# Power_ICs.net
KiCad netlist of a schematic drawn in Altium Designer
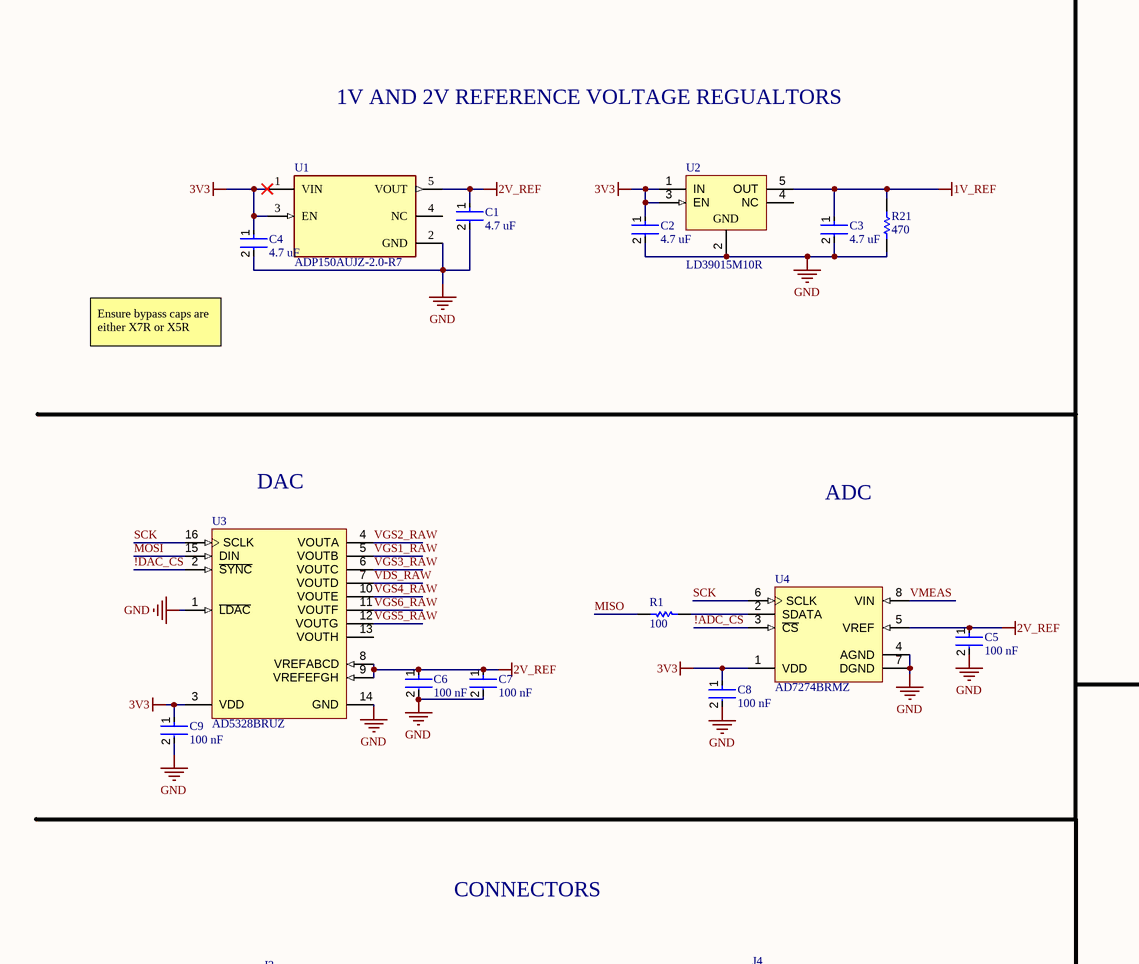
[diagram p0: Power+ICs.SchDoc, top left]
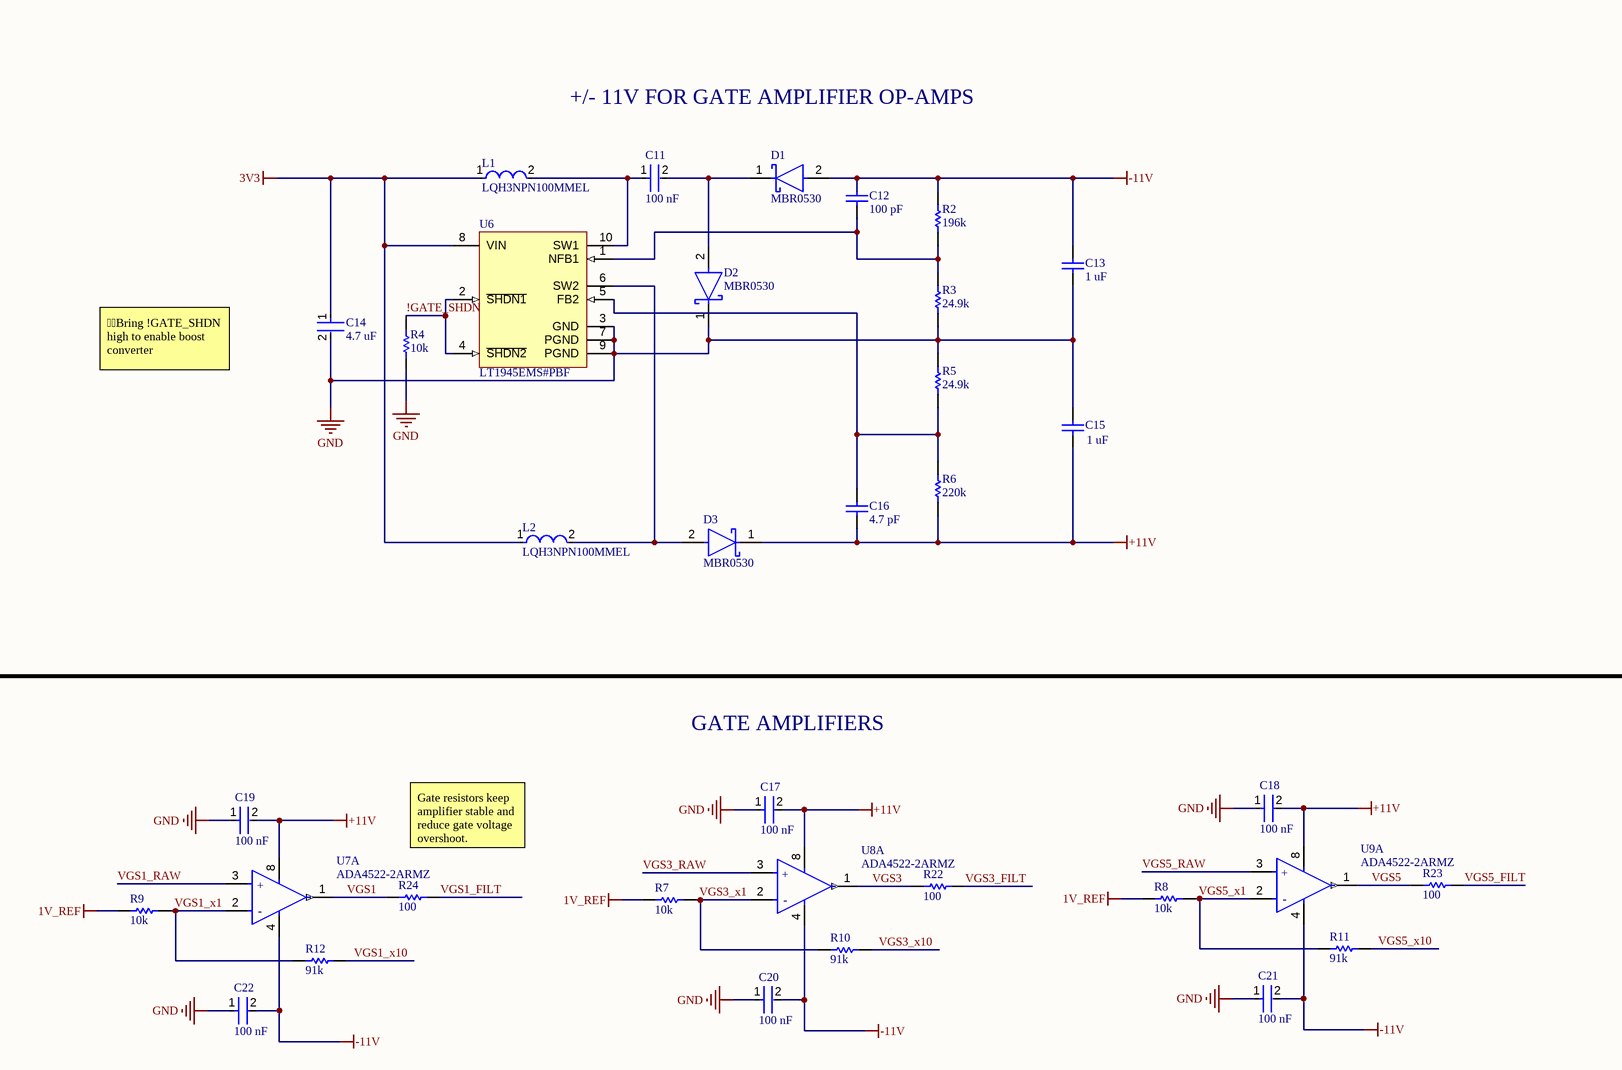
[diagram p1: Power+ICs.SchDoc, top right]
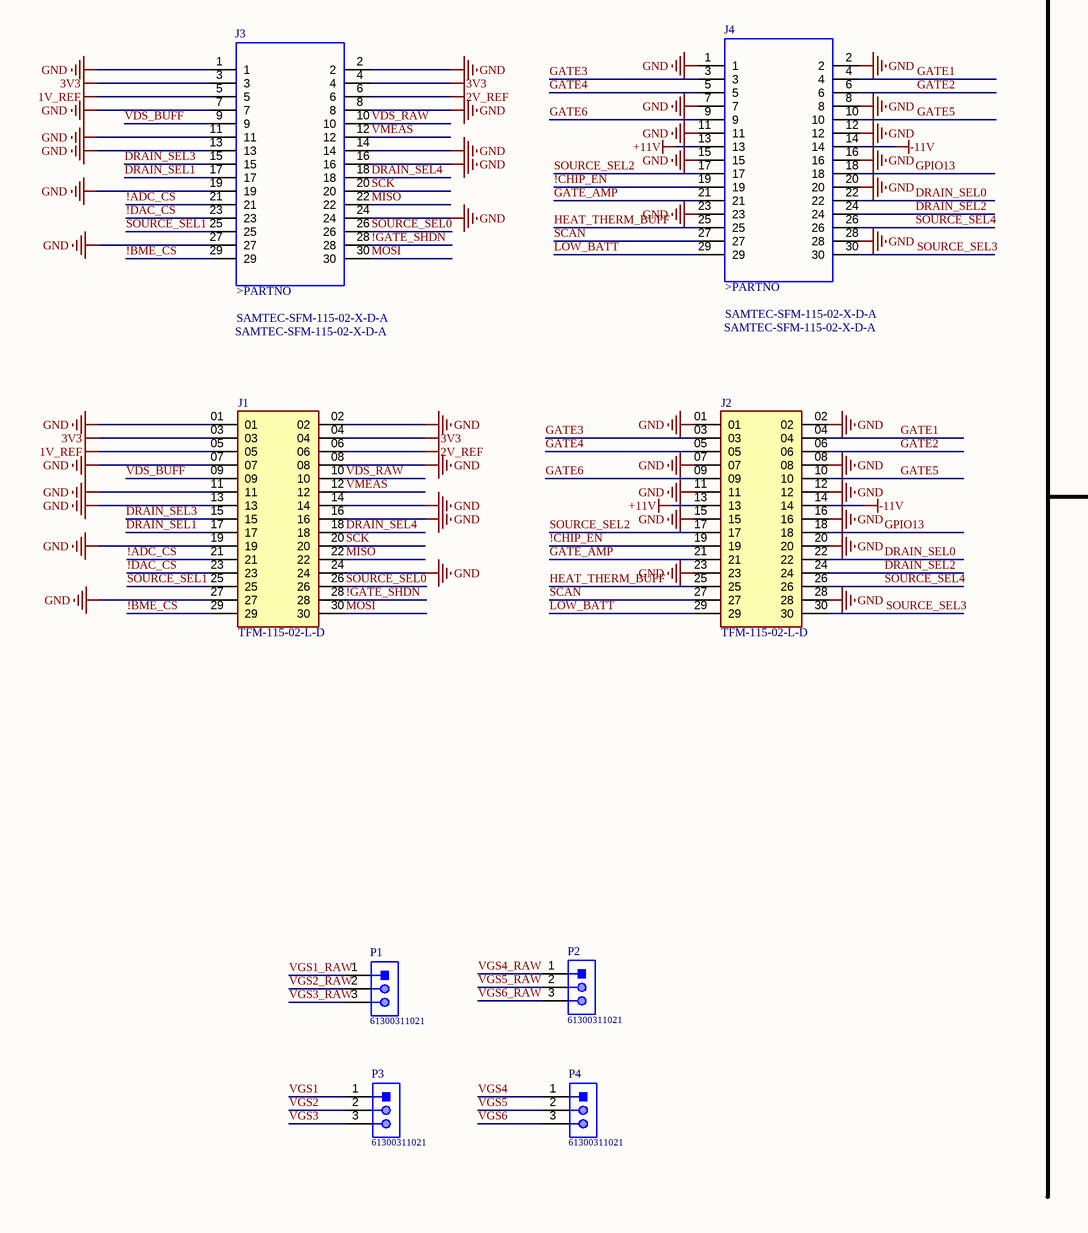
[diagram p2: Power+ICs.SchDoc, bottom left]
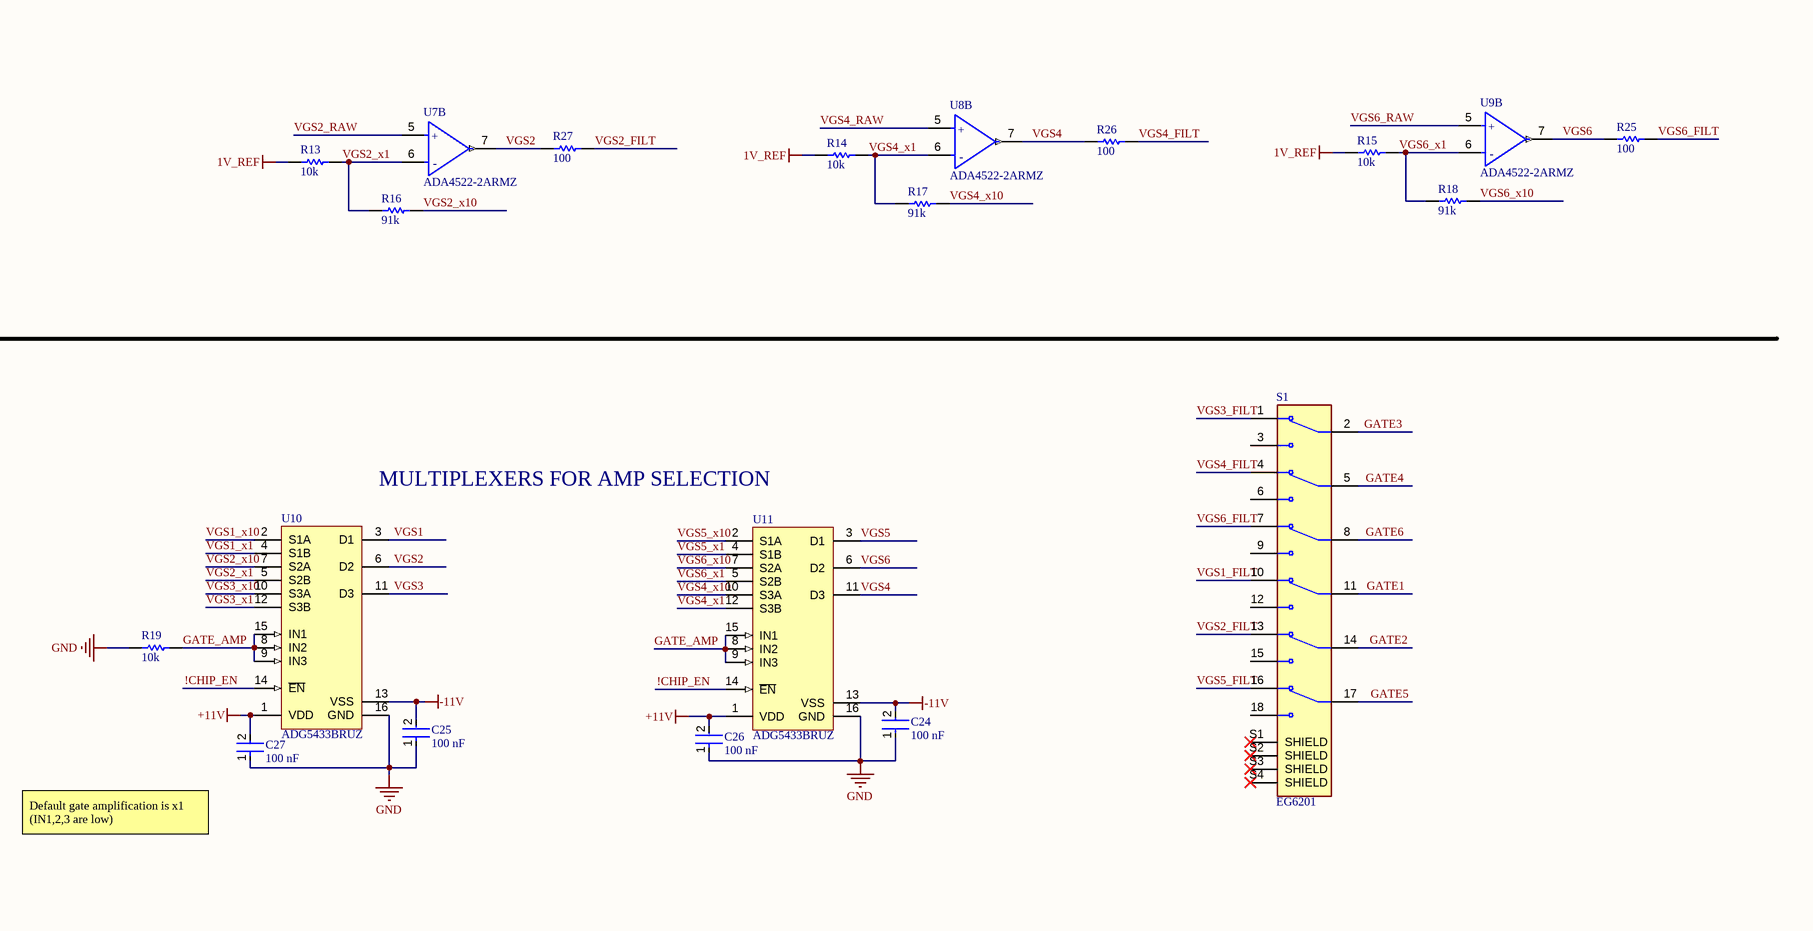
[diagram p3: Power+ICs.SchDoc, bottom right]

(export (version "E")
  (design (tool "Eeschema 10.0.6"))
  (components
    (comp (ref "C1")
      (value "4.7 uF")
      (footprint "FP-C0805C475K3PACTU-MFG")
      (description "CAP CER 4.7UF 25V X5R 0805")
      (fields (field (name "TOLERANCE") "10%") (field (name "VOLTAGE") "25V"))
      (libsource (lib "Altium Content Vault") (part "02cd4be3c70576c341d710602a673aa"))
    )
    (comp (ref "C2")
      (value "4.7 uF")
      (footprint "FP-C0805C475K3PACTU-MFG")
      (description "CAP CER 4.7UF 25V X5R 0805")
      (fields (field (name "TOLERANCE") "10%") (field (name "VOLTAGE") "25V"))
      (libsource (lib "Altium Content Vault") (part "02cd4be3c70576c341d710602a673aa"))
    )
    (comp (ref "C3")
      (value "4.7 uF")
      (footprint "FP-C0805C475K3PACTU-MFG")
      (description "CAP CER 4.7UF 25V X5R 0805")
      (fields (field (name "TOLERANCE") "10%") (field (name "VOLTAGE") "25V"))
      (libsource (lib "Altium Content Vault") (part "02cd4be3c70576c341d710602a673aa"))
    )
    (comp (ref "C4")
      (value "4.7 uF")
      (footprint "FP-C0805C475K3PACTU-MFG")
      (description "CAP CER 4.7UF 25V X5R 0805")
      (fields (field (name "TOLERANCE") "10%") (field (name "VOLTAGE") "25V"))
      (libsource (lib "Altium Content Vault") (part "02cd4be3c70576c341d710602a673aa"))
    )
    (comp (ref "C5")
      (value "100 nF")
      (footprint "FP-C0805C-DN-MFG")
      (description "CAP CER 0.1UF 50V X7R 0805")
      (fields
        (field (name "MANUFACTURER PART NUMBER") "C0805C104K5RACTU")
        (field (name "MANUFACTURER") "KEMET")
      )
      (libsource (lib "Altium Content Vault") (part "b4654b650e69147ec39a6b967a45e02"))
    )
    (comp (ref "C6")
      (value "100 nF")
      (footprint "FP-C0805C-DN-MFG")
      (description "CAP CER 0.1UF 50V X7R 0805")
      (fields
        (field (name "MANUFACTURER PART NUMBER") "C0805C104K5RACTU")
        (field (name "MANUFACTURER") "KEMET")
      )
      (libsource (lib "Altium Content Vault") (part "b4654b650e69147ec39a6b967a45e02"))
    )
    (comp (ref "C7")
      (value "100 nF")
      (footprint "FP-C0805C-DN-MFG")
      (description "CAP CER 0.1UF 50V X7R 0805")
      (fields
        (field (name "MANUFACTURER PART NUMBER") "C0805C104K5RACTU")
        (field (name "MANUFACTURER") "KEMET")
      )
      (libsource (lib "Altium Content Vault") (part "b4654b650e69147ec39a6b967a45e02"))
    )
    (comp (ref "C8")
      (value "100 nF")
      (footprint "FP-C0805C-DN-MFG")
      (description "CAP CER 0.1UF 50V X7R 0805")
      (fields
        (field (name "MANUFACTURER PART NUMBER") "C0805C104K5RACTU")
        (field (name "MANUFACTURER") "KEMET")
      )
      (libsource (lib "Altium Content Vault") (part "b4654b650e69147ec39a6b967a45e02"))
    )
    (comp (ref "C9")
      (value "100 nF")
      (footprint "FP-C0805C-DN-MFG")
      (description "CAP CER 0.1UF 50V X7R 0805")
      (fields
        (field (name "MANUFACTURER PART NUMBER") "C0805C104K5RACTU")
        (field (name "MANUFACTURER") "KEMET")
      )
      (libsource (lib "Altium Content Vault") (part "b4654b650e69147ec39a6b967a45e02"))
    )
    (comp (ref "C11")
      (value "100 nF")
      (footprint "FP-C0805C-DN-MFG")
      (description "CAP CER 0.1UF 50V X7R 0805")
      (fields
        (field (name "MANUFACTURER PART NUMBER") "C0805C104K5RACTU")
        (field (name "MANUFACTURER") "KEMET")
      )
      (libsource (lib "Altium Content Vault") (part "b4654b650e69147ec39a6b967a45e02"))
    )
    (comp (ref "C12")
      (value "100 pF")
      (footprint "CAPC2013X140X50ML20T25")
      (description "08055C101KAT2A")
      (fields (field (name "MANUFACTURER") "AVX Interconnect / Elco"))
      (libsource (lib "Altium Content Vault") (part "CAP"))
    )
    (comp (ref "C13")
      (value "1 uF")
      (footprint "CAPC3216X110X50LL20T25")
      (description "C1206C105K5RACTU")
      (fields (field (name "MANUFACTURER") "Kemet") (field (name "TOLERANCE") "10%"))
      (libsource (lib "Altium Content Vault") (part "CAP-NP-2"))
    )
    (comp (ref "C14")
      (value "4.7 uF")
      (footprint "FP-C0805C475K3PACTU-MFG")
      (description "CAP CER 4.7UF 25V X5R 0805")
      (fields (field (name "TOLERANCE") "10%") (field (name "VOLTAGE") "25V"))
      (libsource (lib "Altium Content Vault") (part "02cd4be3c70576c341d710602a673aa"))
    )
    (comp (ref "C15")
      (value "1 uF")
      (footprint "CAPC3216X110X50LL20T25")
      (description "C1206C105K5RACTU")
      (fields (field (name "MANUFACTURER") "Kemet") (field (name "TOLERANCE") "10%"))
      (libsource (lib "Altium Content Vault") (part "CAP-NP-2"))
    )
    (comp (ref "C16")
      (value "4.7 pF")
      (footprint "CAPC2013X71X50ML20T25")
      (description "08055A4R7CAT2A")
      (fields (field (name "MANUFACTURER") "AVX Interconnect / Elco"))
      (libsource (lib "Altium Content Vault") (part "CAP"))
    )
    (comp (ref "C17")
      (value "100 nF")
      (footprint "FP-C0805C-DN-MFG")
      (description "CAP CER 0.1UF 50V X7R 0805")
      (fields
        (field (name "MANUFACTURER PART NUMBER") "C0805C104K5RACTU")
        (field (name "MANUFACTURER") "KEMET")
      )
      (libsource (lib "Altium Content Vault") (part "b4654b650e69147ec39a6b967a45e02"))
    )
    (comp (ref "C18")
      (value "100 nF")
      (footprint "FP-C0805C-DN-MFG")
      (description "CAP CER 0.1UF 50V X7R 0805")
      (fields
        (field (name "MANUFACTURER PART NUMBER") "C0805C104K5RACTU")
        (field (name "MANUFACTURER") "KEMET")
      )
      (libsource (lib "Altium Content Vault") (part "b4654b650e69147ec39a6b967a45e02"))
    )
    (comp (ref "C19")
      (value "100 nF")
      (footprint "FP-C0805C-DN-MFG")
      (description "CAP CER 0.1UF 50V X7R 0805")
      (fields
        (field (name "MANUFACTURER PART NUMBER") "C0805C104K5RACTU")
        (field (name "MANUFACTURER") "KEMET")
      )
      (libsource (lib "Altium Content Vault") (part "b4654b650e69147ec39a6b967a45e02"))
    )
    (comp (ref "C20")
      (value "100 nF")
      (footprint "FP-C0805C-DN-MFG")
      (description "CAP CER 0.1UF 50V X7R 0805")
      (fields
        (field (name "MANUFACTURER PART NUMBER") "C0805C104K5RACTU")
        (field (name "MANUFACTURER") "KEMET")
      )
      (libsource (lib "Altium Content Vault") (part "b4654b650e69147ec39a6b967a45e02"))
    )
    (comp (ref "C21")
      (value "100 nF")
      (footprint "FP-C0805C-DN-MFG")
      (description "CAP CER 0.1UF 50V X7R 0805")
      (fields
        (field (name "MANUFACTURER PART NUMBER") "C0805C104K5RACTU")
        (field (name "MANUFACTURER") "KEMET")
      )
      (libsource (lib "Altium Content Vault") (part "b4654b650e69147ec39a6b967a45e02"))
    )
    (comp (ref "C22")
      (value "100 nF")
      (footprint "FP-C0805C-DN-MFG")
      (description "CAP CER 0.1UF 50V X7R 0805")
      (fields
        (field (name "MANUFACTURER PART NUMBER") "C0805C104K5RACTU")
        (field (name "MANUFACTURER") "KEMET")
      )
      (libsource (lib "Altium Content Vault") (part "b4654b650e69147ec39a6b967a45e02"))
    )
    (comp (ref "C24")
      (value "100 nF")
      (footprint "FP-C0805C-DN-MFG")
      (description "CAP CER 0.1UF 50V X7R 0805")
      (fields
        (field (name "MANUFACTURER PART NUMBER") "C0805C104K5RACTU")
        (field (name "MANUFACTURER") "KEMET")
      )
      (libsource (lib "Altium Content Vault") (part "b4654b650e69147ec39a6b967a45e02"))
    )
    (comp (ref "C25")
      (value "100 nF")
      (footprint "FP-C0805C-DN-MFG")
      (description "CAP CER 0.1UF 50V X7R 0805")
      (fields
        (field (name "MANUFACTURER PART NUMBER") "C0805C104K5RACTU")
        (field (name "MANUFACTURER") "KEMET")
      )
      (libsource (lib "Altium Content Vault") (part "b4654b650e69147ec39a6b967a45e02"))
    )
    (comp (ref "C26")
      (value "100 nF")
      (footprint "FP-C0805C-DN-MFG")
      (description "CAP CER 0.1UF 50V X7R 0805")
      (fields
        (field (name "MANUFACTURER PART NUMBER") "C0805C104K5RACTU")
        (field (name "MANUFACTURER") "KEMET")
      )
      (libsource (lib "Altium Content Vault") (part "b4654b650e69147ec39a6b967a45e02"))
    )
    (comp (ref "C27")
      (value "100 nF")
      (footprint "FP-C0805C-DN-MFG")
      (description "CAP CER 0.1UF 50V X7R 0805")
      (fields
        (field (name "MANUFACTURER PART NUMBER") "C0805C104K5RACTU")
        (field (name "MANUFACTURER") "KEMET")
      )
      (libsource (lib "Altium Content Vault") (part "b4654b650e69147ec39a6b967a45e02"))
    )
    (comp (ref "D1")
      (value "MBR0530")
      (footprint "FP-425-04-MFG")
      (description "DIODE SCHOTTKY 30V 500MA SOD123")
      (libsource (lib "Altium Content Vault") (part "1d6ec82d83fb6aee721767c19dac4b9"))
    )
    (comp (ref "D2")
      (value "MBR0530")
      (footprint "FP-425-04-MFG")
      (description "DIODE SCHOTTKY 30V 500MA SOD123")
      (libsource (lib "Altium Content Vault") (part "1d6ec82d83fb6aee721767c19dac4b9"))
    )
    (comp (ref "D3")
      (value "MBR0530")
      (footprint "FP-425-04-MFG")
      (description "DIODE SCHOTTKY 30V 500MA SOD123")
      (libsource (lib "Altium Content Vault") (part "1d6ec82d83fb6aee721767c19dac4b9"))
    )
    (comp (ref "J1")
      (value "TFM-115-02-L-D")
      (footprint "SAMTEC_TFM-115-02-L-D:SAMTEC_TFM-115-02-L-D")
      (fields (field (name "MF") "Samtec Inc."))
      (libsource (lib "TFM-115-02-L-D") (part "TFM-115-02-L-D"))
    )
    (comp (ref "J2")
      (value "TFM-115-02-L-D")
      (footprint "SAMTEC_TFM-115-02-L-D:SAMTEC_TFM-115-02-L-D")
      (fields (field (name "MF") "Samtec Inc."))
      (libsource (lib "TFM-115-02-L-D") (part "TFM-115-02-L-D"))
    )
    (comp (ref "J3")
      (value "SAMTEC-SFM-115-02-X-D-A")
      (footprint "SAMTEC-SFM-115-02-X-D-A:SAMTEC-SFM-115-02-X-D-A")
      (fields (field (name "MF") "Samtec Inc."))
      (libsource (lib "SAMTEC-SFM-115-02-X-D-A") (part "SAMTEC-SFM-115-02-X-D-A"))
    )
    (comp (ref "J4")
      (value "SAMTEC-SFM-115-02-X-D-A")
      (footprint "SAMTEC-SFM-115-02-X-D-A:SAMTEC-SFM-115-02-X-D-A")
      (fields (field (name "MF") "Samtec Inc."))
      (libsource (lib "SAMTEC-SFM-115-02-X-D-A") (part "SAMTEC-SFM-115-02-X-D-A"))
    )
    (comp (ref "L1")
      (value "LQH3NPN100MMEL")
      (footprint "FP-LQH3NPH_ME-MFG")
      (description "Wire Wound Ferrite Inductor for Power Lines 10μH ±20% 0.228Ω 1280mA 1212")
      (fields (field (name "TOLERANCE") "20%"))
      (libsource (lib "Altium Content Vault") (part "725321dda6339637d4d059423bc1c3c"))
    )
    (comp (ref "L2")
      (value "LQH3NPN100MMEL")
      (footprint "FP-LQH3NPH_ME-MFG")
      (description "Wire Wound Ferrite Inductor for Power Lines 10μH ±20% 0.228Ω 1280mA 1212")
      (fields (field (name "TOLERANCE") "20%"))
      (libsource (lib "Altium Content Vault") (part "725321dda6339637d4d059423bc1c3c"))
    )
    (comp (ref "P1")
      (value "61300311021")
      (footprint "61300311021")
      (description "THT Angled Pin Header WR-PHD, Pitch 2.54 mm, Single Row, 3 pins")
      (fields (field (name "MANUFACTURER") "Wurth Elektronik") (field (name "PUBLISHER") "WurthElektronik"))
      (libsource (lib "Altium Content Vault") (part "WE-CN-1P-M-R3"))
    )
    (comp (ref "P2")
      (value "61300311021")
      (footprint "61300311021")
      (description "THT Angled Pin Header WR-PHD, Pitch 2.54 mm, Single Row, 3 pins")
      (fields (field (name "MANUFACTURER") "Wurth Elektronik") (field (name "PUBLISHER") "WurthElektronik"))
      (libsource (lib "Altium Content Vault") (part "WE-CN-1P-M-R3"))
    )
    (comp (ref "P3")
      (value "61300311021")
      (footprint "61300311021")
      (description "THT Angled Pin Header WR-PHD, Pitch 2.54 mm, Single Row, 3 pins")
      (fields (field (name "MANUFACTURER") "Wurth Elektronik") (field (name "PUBLISHER") "WurthElektronik"))
      (libsource (lib "Altium Content Vault") (part "WE-CN-1P-M-R3"))
    )
    (comp (ref "P4")
      (value "61300311021")
      (footprint "61300311021")
      (description "THT Angled Pin Header WR-PHD, Pitch 2.54 mm, Single Row, 3 pins")
      (fields (field (name "MANUFACTURER") "Wurth Elektronik") (field (name "PUBLISHER") "WurthElektronik"))
      (libsource (lib "Altium Content Vault") (part "WE-CN-1P-M-R3"))
    )
    (comp (ref "R1")
      (value "100")
      (footprint "RESC2013X50X30LL20T20")
      (fields (field (name "MANUFACTURER") "Vishay Dale") (field (name "PART NUMBER") "CRCW0805100RFKEA"))
      (libsource (lib "Altium Content Vault") (part "RES"))
    )
    (comp (ref "R2")
      (value "196k")
      (footprint "RESC2013X50X30LL20T20")
      (fields (field (name "MANUFACTURER") "Vishay Dale") (field (name "PART NUMBER") "CRCW0805196KFKEA"))
      (libsource (lib "Altium Content Vault") (part "RES"))
    )
    (comp (ref "R3")
      (value "24.9k")
      (footprint "RESC2013X70X40LL20T20")
      (fields (field (name "PART NUMBER") "ERJ-6ENF2492V") (field (name "MANUFACTURER") "Panasonic"))
      (libsource (lib "Altium Content Vault") (part "RES"))
    )
    (comp (ref "R4")
      (value "10k")
      (footprint "RESC2013X60X35NL10T20")
      (description "Chip Resistor, 10 KOhm, +/- 1%, 0.125 W, -55 to 155 degC, 0805 (2012 Metric), RoHS, Tape and Reel")
      (fields (field (name "MANUFACTURER") "Yageo"))
      (libsource (lib "Altium Content Vault") (part "RES-2"))
    )
    (comp (ref "R5")
      (value "24.9k")
      (footprint "RESC2013X70X40LL20T20")
      (fields (field (name "PART NUMBER") "ERJ-6ENF2492V") (field (name "MANUFACTURER") "Panasonic"))
      (libsource (lib "Altium Content Vault") (part "RES"))
    )
    (comp (ref "R6")
      (value "220k")
      (footprint "RESC2013X70X40ML20T20")
      (fields (field (name "PART NUMBER") "ERJ6ENF2203V") (field (name "MANUFACTURER") "Panasonic"))
      (libsource (lib "Altium Content Vault") (part "RES"))
    )
    (comp (ref "R7")
      (value "10k")
      (footprint "RESC2013X60X35NL10T20")
      (description "Chip Resistor, 10 KOhm, +/- 1%, 0.125 W, -55 to 155 degC, 0805 (2012 Metric), RoHS, Tape and Reel")
      (fields (field (name "MANUFACTURER") "Yageo"))
      (libsource (lib "Altium Content Vault") (part "RES-2"))
    )
    (comp (ref "R8")
      (value "10k")
      (footprint "RESC2013X60X35NL10T20")
      (description "Chip Resistor, 10 KOhm, +/- 1%, 0.125 W, -55 to 155 degC, 0805 (2012 Metric), RoHS, Tape and Reel")
      (fields (field (name "MANUFACTURER") "Yageo"))
      (libsource (lib "Altium Content Vault") (part "RES-2"))
    )
    (comp (ref "R9")
      (value "10k")
      (footprint "RESC2013X60X35NL10T20")
      (description "Chip Resistor, 10 KOhm, +/- 1%, 0.125 W, -55 to 155 degC, 0805 (2012 Metric), RoHS, Tape and Reel")
      (fields (field (name "MANUFACTURER") "Yageo"))
      (libsource (lib "Altium Content Vault") (part "RES-2"))
    )
    (comp (ref "R10")
      (value "91k")
      (footprint "RESC2013X60X35ML10T20")
      (fields (field (name "PART NUMBER") "RC0805JR-0791KL") (field (name "MANUFACTURER") "Yageo"))
      (libsource (lib "Altium Content Vault") (part "RES"))
    )
    (comp (ref "R11")
      (value "91k")
      (footprint "RESC2013X60X35ML10T20")
      (fields (field (name "PART NUMBER") "RC0805JR-0791KL") (field (name "MANUFACTURER") "Yageo"))
      (libsource (lib "Altium Content Vault") (part "RES"))
    )
    (comp (ref "R12")
      (value "91k")
      (footprint "RESC2013X60X35ML10T20")
      (fields (field (name "PART NUMBER") "RC0805JR-0791KL") (field (name "MANUFACTURER") "Yageo"))
      (libsource (lib "Altium Content Vault") (part "RES"))
    )
    (comp (ref "R13")
      (value "10k")
      (footprint "RESC2013X60X35NL10T20")
      (description "Chip Resistor, 10 KOhm, +/- 1%, 0.125 W, -55 to 155 degC, 0805 (2012 Metric), RoHS, Tape and Reel")
      (fields (field (name "MANUFACTURER") "Yageo"))
      (libsource (lib "Altium Content Vault") (part "RES-2"))
    )
    (comp (ref "R14")
      (value "10k")
      (footprint "RESC2013X60X35NL10T20")
      (description "Chip Resistor, 10 KOhm, +/- 1%, 0.125 W, -55 to 155 degC, 0805 (2012 Metric), RoHS, Tape and Reel")
      (fields (field (name "MANUFACTURER") "Yageo"))
      (libsource (lib "Altium Content Vault") (part "RES-2"))
    )
    (comp (ref "R15")
      (value "10k")
      (footprint "RESC2013X60X35NL10T20")
      (description "Chip Resistor, 10 KOhm, +/- 1%, 0.125 W, -55 to 155 degC, 0805 (2012 Metric), RoHS, Tape and Reel")
      (fields (field (name "MANUFACTURER") "Yageo"))
      (libsource (lib "Altium Content Vault") (part "RES-2"))
    )
    (comp (ref "R16")
      (value "91k")
      (footprint "RESC2013X60X35ML10T20")
      (fields (field (name "PART NUMBER") "RC0805JR-0791KL") (field (name "MANUFACTURER") "Yageo"))
      (libsource (lib "Altium Content Vault") (part "RES"))
    )
    (comp (ref "R17")
      (value "91k")
      (footprint "RESC2013X60X35ML10T20")
      (fields (field (name "PART NUMBER") "RC0805JR-0791KL") (field (name "MANUFACTURER") "Yageo"))
      (libsource (lib "Altium Content Vault") (part "RES"))
    )
    (comp (ref "R18")
      (value "91k")
      (footprint "RESC2013X60X35ML10T20")
      (fields (field (name "PART NUMBER") "RC0805JR-0791KL") (field (name "MANUFACTURER") "Yageo"))
      (libsource (lib "Altium Content Vault") (part "RES"))
    )
    (comp (ref "R19")
      (value "10k")
      (footprint "RESC2013X60X35NL10T20")
      (description "Chip Resistor, 10 KOhm, +/- 1%, 0.125 W, -55 to 155 degC, 0805 (2012 Metric), RoHS, Tape and Reel")
      (fields (field (name "MANUFACTURER") "Yageo"))
      (libsource (lib "Altium Content Vault") (part "RES-2"))
    )
    (comp (ref "R21")
      (value "470")
      (footprint "RESC2013X70X40ML20T20")
      (description "Chip Resistor, 470 Ohm, +/- 1%, 0.125 W, -55 to 155 degC, 0805 (2012 Metric), RoHS, Tape and Reel")
      (fields (field (name "MANUFACTURER") "Panasonic"))
      (libsource (lib "Altium Content Vault") (part "RES-2"))
    )
    (comp (ref "R22")
      (value "100")
      (footprint "RESC2013X50X30LL20T20")
      (fields (field (name "MANUFACTURER") "Vishay Dale") (field (name "PART NUMBER") "CRCW0805100RFKEA"))
      (libsource (lib "Altium Content Vault") (part "RES"))
    )
    (comp (ref "R23")
      (value "100")
      (footprint "RESC2013X50X30LL20T20")
      (fields (field (name "MANUFACTURER") "Vishay Dale") (field (name "PART NUMBER") "CRCW0805100RFKEA"))
      (libsource (lib "Altium Content Vault") (part "RES"))
    )
    (comp (ref "R24")
      (value "100")
      (footprint "RESC2013X50X30LL20T20")
      (fields (field (name "MANUFACTURER") "Vishay Dale") (field (name "PART NUMBER") "CRCW0805100RFKEA"))
      (libsource (lib "Altium Content Vault") (part "RES"))
    )
    (comp (ref "R25")
      (value "100")
      (footprint "RESC2013X50X30LL20T20")
      (fields (field (name "MANUFACTURER") "Vishay Dale") (field (name "PART NUMBER") "CRCW0805100RFKEA"))
      (libsource (lib "Altium Content Vault") (part "RES"))
    )
    (comp (ref "R26")
      (value "100")
      (footprint "RESC2013X50X30LL20T20")
      (fields (field (name "MANUFACTURER") "Vishay Dale") (field (name "PART NUMBER") "CRCW0805100RFKEA"))
      (libsource (lib "Altium Content Vault") (part "RES"))
    )
    (comp (ref "R27")
      (value "100")
      (footprint "RESC2013X50X30LL20T20")
      (fields (field (name "MANUFACTURER") "Vishay Dale") (field (name "PART NUMBER") "CRCW0805100RFKEA"))
      (libsource (lib "Altium Content Vault") (part "RES"))
    )
    (comp (ref "S1")
      (value "EG6201")
      (footprint "SnapEDApcb:SW_EG6201")
      (description "Slide Switch 6PDT Through Hole, Right Angle")
      (fields (field (name "MF") "E-Switch"))
      (libsource (lib "SnapEDAsch") (part "EG6201"))
    )
    (comp (ref "U1")
      (value "ADP150AUJZ-2.0-R7")
      (footprint "FP-UJ-5-IPC_B")
      (description "IC REG LINEAR 2V 150MA 5TSOT")
      (libsource (lib "Altium Content Vault") (part "038a824adfd04a965d73cdd9fb88cf2"))
    )
    (comp (ref "U2")
      (value "LD39015M10R")
      (footprint "SOT23-5L_M")
      (description "150 mA Low Quiescent Current Low Noise Voltage Regulator, 1.0V, 5-Pin SOT-23, Tape and Reel")
      (libsource (lib "Altium Content Vault") (part "PM-REG-LD39015M-SOT5"))
    )
    (comp (ref "U3")
      (value "AD5328BRUZ")
      (footprint "RU-16_L")
      (fields (field (name "GENERIC PART NUMBER") "AD5328") (field (name "MANUFACTURER") "Analog Devices"))
      (libsource (lib "Altium Content Vault") (part "ADI-AD5328-RU-16"))
    )
    (comp (ref "U4")
      (value "AD7274BRMZ")
      (footprint "RM-8_N")
      (fields (field (name "GENERIC PART NUMBER") "AD7274") (field (name "MANUFACTURER") "Analog Devices"))
      (libsource (lib "Altium Content Vault") (part "ADI-AD7274-RM-8"))
    )
    (comp (ref "U6")
      (value "LT1945EMS#PBF")
      (footprint "LT-MS-10_N")
      (fields (field (name "MANUFACTURER") "Linear Technology"))
      (libsource (lib "Altium Content Vault") (part "LT-LT1945-MS-10"))
    )
    (comp (ref "U7")
      (value "ADA4522-2ARMZ")
      (footprint "FP-RM-8-IPC_C")
      (description "IC OPAMP ZERO-DRIFT 2 CIRC 8MSOP")
      (libsource (lib "Altium Content Vault") (part "e8c52d48d03680a0ba04c611cf3b55d"))
    )
    (comp (ref "U8")
      (value "ADA4522-2ARMZ")
      (footprint "FP-RM-8-IPC_C")
      (description "IC OPAMP ZERO-DRIFT 2 CIRC 8MSOP")
      (libsource (lib "Altium Content Vault") (part "e8c52d48d03680a0ba04c611cf3b55d"))
    )
    (comp (ref "U9")
      (value "ADA4522-2ARMZ")
      (footprint "FP-RM-8-IPC_C")
      (description "IC OPAMP ZERO-DRIFT 2 CIRC 8MSOP")
      (libsource (lib "Altium Content Vault") (part "e8c52d48d03680a0ba04c611cf3b55d"))
    )
    (comp (ref "U10")
      (value "ADG5433BRUZ")
      (footprint "ADI-RU-16_N")
      (description "High Voltage Latch-Up Proof, Triple SPDT Switches, 12.5 Ohm Ron, 16-pin SOP (RU-16), Tube")
      (fields (field (name "MANUFACTURER") "Analog Devices"))
      (libsource (lib "Altium Content Vault") (part "ADI-ADG5433-RU-16"))
    )
    (comp (ref "U11")
      (value "ADG5433BRUZ")
      (footprint "ADI-RU-16_N")
      (description "High Voltage Latch-Up Proof, Triple SPDT Switches, 12.5 Ohm Ron, 16-pin SOP (RU-16), Tube")
      (fields (field (name "MANUFACTURER") "Analog Devices"))
      (libsource (lib "Altium Content Vault") (part "ADI-ADG5433-RU-16"))
    )
  )
  (nets
    (net (code "1") (name "+11V") (class "Default")
      (node (ref "C15") (pin "1") (pinfunction "1_1") (pintype "passive"))
      (node (ref "C16") (pin "1") (pinfunction "1_1") (pintype "passive"))
      (node (ref "C17") (pin "2") (pinfunction "2_2") (pintype "passive"))
      (node (ref "C18") (pin "2") (pinfunction "2_2") (pintype "passive"))
      (node (ref "C19") (pin "2") (pinfunction "2_2") (pintype "passive"))
      (node (ref "C26") (pin "2") (pinfunction "2_2") (pintype "passive"))
      (node (ref "C27") (pin "2") (pinfunction "2_2") (pintype "passive"))
      (node (ref "D3") (pin "1") (pinfunction "C_1") (pintype "passive"))
      (node (ref "J2") (pin "13") (pinfunction "13_13") (pintype "passive"))
      (node (ref "J4") (pin "13") (pinfunction "13_13") (pintype "passive"))
      (node (ref "R6") (pin "1") (pinfunction "1_1") (pintype "passive"))
      (node (ref "U10") (pin "1") (pinfunction "VDD_1") (pintype "power_in"))
      (node (ref "U11") (pin "1") (pinfunction "VDD_1") (pintype "power_in"))
      (node (ref "U7") (pin "8") (pinfunction "V+_8") (pintype "power_in"))
      (node (ref "U8") (pin "8") (pinfunction "V+_8") (pintype "power_in"))
      (node (ref "U9") (pin "8") (pinfunction "V+_8") (pintype "power_in"))
    )
    (net (code "2") (name "-11V") (class "Default")
      (node (ref "C12") (pin "1") (pinfunction "1_1") (pintype "passive"))
      (node (ref "C13") (pin "2") (pinfunction "2_2") (pintype "passive"))
      (node (ref "C20") (pin "2") (pinfunction "2_2") (pintype "passive"))
      (node (ref "C21") (pin "2") (pinfunction "2_2") (pintype "passive"))
      (node (ref "C22") (pin "2") (pinfunction "2_2") (pintype "passive"))
      (node (ref "C24") (pin "2") (pinfunction "2_2") (pintype "passive"))
      (node (ref "C25") (pin "2") (pinfunction "2_2") (pintype "passive"))
      (node (ref "D1") (pin "2") (pinfunction "A_2") (pintype "passive"))
      (node (ref "J2") (pin "14") (pinfunction "14_14") (pintype "passive"))
      (node (ref "J4") (pin "14") (pinfunction "14_14") (pintype "passive"))
      (node (ref "R2") (pin "2") (pinfunction "2_2") (pintype "passive"))
      (node (ref "U10") (pin "13") (pinfunction "VSS_13") (pintype "power_in"))
      (node (ref "U11") (pin "13") (pinfunction "VSS_13") (pintype "power_in"))
      (node (ref "U7") (pin "4") (pinfunction "V-_4") (pintype "power_in"))
      (node (ref "U8") (pin "4") (pinfunction "V-_4") (pintype "power_in"))
      (node (ref "U9") (pin "4") (pinfunction "V-_4") (pintype "power_in"))
    )
    (net (code "3") (name "/!ADC_CS") (class "Default")
      (node (ref "J1") (pin "21") (pinfunction "21_21") (pintype "passive"))
      (node (ref "J3") (pin "21") (pinfunction "21_21") (pintype "passive"))
      (node (ref "U4") (pin "3") (pinfunction "~{CS}_3") (pintype "input"))
    )
    (net (code "4") (name "/!BME_CS") (class "Default")
      (node (ref "J1") (pin "29") (pinfunction "29_29") (pintype "passive"))
      (node (ref "J3") (pin "29") (pinfunction "29_29") (pintype "passive"))
    )
    (net (code "5") (name "/!CHIP_EN") (class "Default")
      (node (ref "J2") (pin "19") (pinfunction "19_19") (pintype "passive"))
      (node (ref "J4") (pin "19") (pinfunction "19_19") (pintype "passive"))
      (node (ref "U10") (pin "14") (pinfunction "~{EN}_14") (pintype "input"))
      (node (ref "U11") (pin "14") (pinfunction "~{EN}_14") (pintype "input"))
    )
    (net (code "6") (name "/!DAC_CS") (class "Default")
      (node (ref "J1") (pin "23") (pinfunction "23_23") (pintype "passive"))
      (node (ref "J3") (pin "23") (pinfunction "23_23") (pintype "passive"))
      (node (ref "U3") (pin "2") (pinfunction "~{SYNC}_2") (pintype "input"))
    )
    (net (code "7") (name "/!GATE_SHDN") (class "Default")
      (node (ref "J1") (pin "28") (pinfunction "28_28") (pintype "passive"))
      (node (ref "J3") (pin "28") (pinfunction "28_28") (pintype "passive"))
      (node (ref "R4") (pin "2") (pinfunction "2_2") (pintype "passive"))
      (node (ref "U6") (pin "2") (pinfunction "~{SHDN1}_2") (pintype "input"))
      (node (ref "U6") (pin "4") (pinfunction "~{SHDN2}_4") (pintype "input"))
    )
    (net (code "8") (name "/DRAIN_SEL0") (class "Default")
      (node (ref "J2") (pin "22") (pinfunction "22_22") (pintype "passive"))
      (node (ref "J4") (pin "22") (pinfunction "22_22") (pintype "passive"))
    )
    (net (code "9") (name "/DRAIN_SEL1") (class "Default")
      (node (ref "J1") (pin "17") (pinfunction "17_17") (pintype "passive"))
      (node (ref "J3") (pin "17") (pinfunction "17_17") (pintype "passive"))
    )
    (net (code "10") (name "/DRAIN_SEL2") (class "Default")
      (node (ref "J2") (pin "24") (pinfunction "24_24") (pintype "passive"))
      (node (ref "J4") (pin "24") (pinfunction "24_24") (pintype "passive"))
    )
    (net (code "11") (name "/DRAIN_SEL3") (class "Default")
      (node (ref "J1") (pin "15") (pinfunction "15_15") (pintype "passive"))
      (node (ref "J3") (pin "15") (pinfunction "15_15") (pintype "passive"))
    )
    (net (code "12") (name "/DRAIN_SEL4") (class "Default")
      (node (ref "J1") (pin "18") (pinfunction "18_18") (pintype "passive"))
      (node (ref "J3") (pin "18") (pinfunction "18_18") (pintype "passive"))
    )
    (net (code "13") (name "/GATE1") (class "Default")
      (node (ref "J2") (pin "04") (pinfunction "04_04") (pintype "passive"))
      (node (ref "J4") (pin "4") (pinfunction "4_4") (pintype "passive"))
      (node (ref "S1") (pin "11") (pinfunction "COM4_11") (pintype "passive"))
    )
    (net (code "14") (name "/GATE2") (class "Default")
      (node (ref "J2") (pin "06") (pinfunction "06_06") (pintype "passive"))
      (node (ref "J4") (pin "6") (pinfunction "6_6") (pintype "passive"))
      (node (ref "S1") (pin "14") (pinfunction "COM5_14") (pintype "passive"))
    )
    (net (code "15") (name "/GATE3") (class "Default")
      (node (ref "J2") (pin "03") (pinfunction "03_03") (pintype "passive"))
      (node (ref "J4") (pin "3") (pinfunction "3_3") (pintype "passive"))
      (node (ref "S1") (pin "2") (pinfunction "COM1_2") (pintype "passive"))
    )
    (net (code "16") (name "/GATE4") (class "Default")
      (node (ref "J2") (pin "05") (pinfunction "05_05") (pintype "passive"))
      (node (ref "J4") (pin "5") (pinfunction "5_5") (pintype "passive"))
      (node (ref "S1") (pin "5") (pinfunction "COM2_5") (pintype "passive"))
    )
    (net (code "17") (name "/GATE5") (class "Default")
      (node (ref "J2") (pin "10") (pinfunction "10_10") (pintype "passive"))
      (node (ref "J4") (pin "10") (pinfunction "10_10") (pintype "passive"))
      (node (ref "S1") (pin "17") (pinfunction "COM6_17") (pintype "passive"))
    )
    (net (code "18") (name "/GATE6") (class "Default")
      (node (ref "J2") (pin "09") (pinfunction "09_09") (pintype "passive"))
      (node (ref "J4") (pin "9") (pinfunction "9_9") (pintype "passive"))
      (node (ref "S1") (pin "8") (pinfunction "COM3_8") (pintype "passive"))
    )
    (net (code "19") (name "/GATE_AMP") (class "Default")
      (node (ref "J2") (pin "21") (pinfunction "21_21") (pintype "passive"))
      (node (ref "J4") (pin "21") (pinfunction "21_21") (pintype "passive"))
      (node (ref "R19") (pin "1") (pinfunction "1_1") (pintype "passive"))
      (node (ref "U10") (pin "15") (pinfunction "IN1_15") (pintype "input"))
      (node (ref "U10") (pin "8") (pinfunction "IN2_8") (pintype "input"))
      (node (ref "U10") (pin "9") (pinfunction "IN3_9") (pintype "input"))
      (node (ref "U11") (pin "15") (pinfunction "IN1_15") (pintype "input"))
      (node (ref "U11") (pin "8") (pinfunction "IN2_8") (pintype "input"))
      (node (ref "U11") (pin "9") (pinfunction "IN3_9") (pintype "input"))
    )
    (net (code "20") (name "/GPIO13") (class "Default")
      (node (ref "J2") (pin "18") (pinfunction "18_18") (pintype "passive"))
      (node (ref "J4") (pin "18") (pinfunction "18_18") (pintype "passive"))
    )
    (net (code "21") (name "/HEAT_THERM_BUFF") (class "Default")
      (node (ref "J2") (pin "25") (pinfunction "25_25") (pintype "passive"))
      (node (ref "J4") (pin "25") (pinfunction "25_25") (pintype "passive"))
    )
    (net (code "22") (name "/LOW_BATT") (class "Default")
      (node (ref "J2") (pin "29") (pinfunction "29_29") (pintype "passive"))
      (node (ref "J4") (pin "29") (pinfunction "29_29") (pintype "passive"))
    )
    (net (code "23") (name "/MISO") (class "Default")
      (node (ref "J1") (pin "22") (pinfunction "22_22") (pintype "passive"))
      (node (ref "J3") (pin "22") (pinfunction "22_22") (pintype "passive"))
      (node (ref "R1") (pin "2") (pinfunction "2_2") (pintype "passive"))
    )
    (net (code "24") (name "/MOSI") (class "Default")
      (node (ref "J1") (pin "30") (pinfunction "30_30") (pintype "passive"))
      (node (ref "J3") (pin "30") (pinfunction "30_30") (pintype "passive"))
      (node (ref "U3") (pin "15") (pinfunction "DIN_15") (pintype "input"))
    )
    (net (code "25") (name "/SCAN") (class "Default")
      (node (ref "J2") (pin "27") (pinfunction "27_27") (pintype "passive"))
      (node (ref "J4") (pin "27") (pinfunction "27_27") (pintype "passive"))
    )
    (net (code "26") (name "/SCK") (class "Default")
      (node (ref "J1") (pin "20") (pinfunction "20_20") (pintype "passive"))
      (node (ref "J3") (pin "20") (pinfunction "20_20") (pintype "passive"))
      (node (ref "U3") (pin "16") (pinfunction "SCLK_16") (pintype "input"))
      (node (ref "U4") (pin "6") (pinfunction "SCLK_6") (pintype "input"))
    )
    (net (code "27") (name "/SOURCE_SEL0") (class "Default")
      (node (ref "J1") (pin "26") (pinfunction "26_26") (pintype "passive"))
      (node (ref "J3") (pin "26") (pinfunction "26_26") (pintype "passive"))
    )
    (net (code "28") (name "/SOURCE_SEL1") (class "Default")
      (node (ref "J1") (pin "25") (pinfunction "25_25") (pintype "passive"))
      (node (ref "J3") (pin "25") (pinfunction "25_25") (pintype "passive"))
    )
    (net (code "29") (name "/SOURCE_SEL2") (class "Default")
      (node (ref "J2") (pin "17") (pinfunction "17_17") (pintype "passive"))
      (node (ref "J4") (pin "17") (pinfunction "17_17") (pintype "passive"))
    )
    (net (code "30") (name "/SOURCE_SEL3") (class "Default")
      (node (ref "J2") (pin "30") (pinfunction "30_30") (pintype "passive"))
      (node (ref "J4") (pin "30") (pinfunction "30_30") (pintype "passive"))
    )
    (net (code "31") (name "/SOURCE_SEL4") (class "Default")
      (node (ref "J2") (pin "26") (pinfunction "26_26") (pintype "passive"))
      (node (ref "J4") (pin "26") (pinfunction "26_26") (pintype "passive"))
    )
    (net (code "32") (name "/VDS_BUFF") (class "Default")
      (node (ref "J1") (pin "09") (pinfunction "09_09") (pintype "passive"))
      (node (ref "J3") (pin "9") (pinfunction "9_9") (pintype "passive"))
    )
    (net (code "33") (name "/VDS_RAW") (class "Default")
      (node (ref "J1") (pin "10") (pinfunction "10_10") (pintype "passive"))
      (node (ref "J3") (pin "10") (pinfunction "10_10") (pintype "passive"))
      (node (ref "U3") (pin "7") (pinfunction "VOUTD_7") (pintype "tri_state"))
    )
    (net (code "34") (name "/VGS1") (class "Default")
      (node (ref "P3") (pin "1") (pinfunction "1_1") (pintype "passive"))
      (node (ref "R24") (pin "1") (pinfunction "1_1") (pintype "passive"))
      (node (ref "U10") (pin "3") (pinfunction "D1_3") (pintype "passive"))
      (node (ref "U7") (pin "1") (pinfunction "OUT_A_1") (pintype "output"))
    )
    (net (code "35") (name "/VGS1_FILT") (class "Default")
      (node (ref "R24") (pin "2") (pinfunction "2_2") (pintype "passive"))
      (node (ref "S1") (pin "10") (pinfunction "NC4_10") (pintype "passive"))
    )
    (net (code "36") (name "/VGS1_RAW") (class "Default")
      (node (ref "P1") (pin "1") (pinfunction "1_1") (pintype "passive"))
      (node (ref "U3") (pin "5") (pinfunction "VOUTB_5") (pintype "tri_state"))
      (node (ref "U7") (pin "3") (pinfunction "+IN_A_3") (pintype "tri_state"))
    )
    (net (code "37") (name "/VGS1_x1") (class "Default")
      (node (ref "R12") (pin "1") (pinfunction "1_1") (pintype "passive"))
      (node (ref "R9") (pin "1") (pinfunction "1_1") (pintype "passive"))
      (node (ref "U10") (pin "4") (pinfunction "S1B_4") (pintype "passive"))
      (node (ref "U7") (pin "2") (pinfunction "-IN_A_2") (pintype "tri_state"))
    )
    (net (code "38") (name "/VGS1_x10") (class "Default")
      (node (ref "R12") (pin "2") (pinfunction "2_2") (pintype "passive"))
      (node (ref "U10") (pin "2") (pinfunction "S1A_2") (pintype "passive"))
    )
    (net (code "39") (name "/VGS2") (class "Default")
      (node (ref "P3") (pin "2") (pinfunction "2_2") (pintype "passive"))
      (node (ref "R27") (pin "1") (pinfunction "1_1") (pintype "passive"))
      (node (ref "U10") (pin "6") (pinfunction "D2_6") (pintype "passive"))
      (node (ref "U7") (pin "7") (pinfunction "OUT_B_7") (pintype "output"))
    )
    (net (code "40") (name "/VGS2_FILT") (class "Default")
      (node (ref "R27") (pin "2") (pinfunction "2_2") (pintype "passive"))
      (node (ref "S1") (pin "13") (pinfunction "NC5_13") (pintype "passive"))
    )
    (net (code "41") (name "/VGS2_RAW") (class "Default")
      (node (ref "P1") (pin "2") (pinfunction "2_2") (pintype "passive"))
      (node (ref "U3") (pin "4") (pinfunction "VOUTA_4") (pintype "tri_state"))
      (node (ref "U7") (pin "5") (pinfunction "+IN_B_5") (pintype "tri_state"))
    )
    (net (code "42") (name "/VGS2_x1") (class "Default")
      (node (ref "R13") (pin "1") (pinfunction "1_1") (pintype "passive"))
      (node (ref "R16") (pin "1") (pinfunction "1_1") (pintype "passive"))
      (node (ref "U10") (pin "5") (pinfunction "S2B_5") (pintype "passive"))
      (node (ref "U7") (pin "6") (pinfunction "-IN_B_6") (pintype "tri_state"))
    )
    (net (code "43") (name "/VGS2_x10") (class "Default")
      (node (ref "R16") (pin "2") (pinfunction "2_2") (pintype "passive"))
      (node (ref "U10") (pin "7") (pinfunction "S2A_7") (pintype "passive"))
    )
    (net (code "44") (name "/VGS3") (class "Default")
      (node (ref "P3") (pin "3") (pinfunction "3_3") (pintype "passive"))
      (node (ref "R22") (pin "1") (pinfunction "1_1") (pintype "passive"))
      (node (ref "U10") (pin "11") (pinfunction "D3_11") (pintype "passive"))
      (node (ref "U8") (pin "1") (pinfunction "OUT_A_1") (pintype "output"))
    )
    (net (code "45") (name "/VGS3_FILT") (class "Default")
      (node (ref "R22") (pin "2") (pinfunction "2_2") (pintype "passive"))
      (node (ref "S1") (pin "1") (pinfunction "NC1_1") (pintype "passive"))
    )
    (net (code "46") (name "/VGS3_RAW") (class "Default")
      (node (ref "P1") (pin "3") (pinfunction "3_3") (pintype "passive"))
      (node (ref "U3") (pin "6") (pinfunction "VOUTC_6") (pintype "tri_state"))
      (node (ref "U8") (pin "3") (pinfunction "+IN_A_3") (pintype "tri_state"))
    )
    (net (code "47") (name "/VGS3_x1") (class "Default")
      (node (ref "R10") (pin "1") (pinfunction "1_1") (pintype "passive"))
      (node (ref "R7") (pin "1") (pinfunction "1_1") (pintype "passive"))
      (node (ref "U10") (pin "12") (pinfunction "S3B_12") (pintype "passive"))
      (node (ref "U8") (pin "2") (pinfunction "-IN_A_2") (pintype "tri_state"))
    )
    (net (code "48") (name "/VGS3_x10") (class "Default")
      (node (ref "R10") (pin "2") (pinfunction "2_2") (pintype "passive"))
      (node (ref "U10") (pin "10") (pinfunction "S3A_10") (pintype "passive"))
    )
    (net (code "49") (name "/VGS4") (class "Default")
      (node (ref "P4") (pin "1") (pinfunction "1_1") (pintype "passive"))
      (node (ref "R26") (pin "1") (pinfunction "1_1") (pintype "passive"))
      (node (ref "U11") (pin "11") (pinfunction "D3_11") (pintype "passive"))
      (node (ref "U8") (pin "7") (pinfunction "OUT_B_7") (pintype "output"))
    )
    (net (code "50") (name "/VGS4_FILT") (class "Default")
      (node (ref "R26") (pin "2") (pinfunction "2_2") (pintype "passive"))
      (node (ref "S1") (pin "4") (pinfunction "NC2_4") (pintype "passive"))
    )
    (net (code "51") (name "/VGS4_RAW") (class "Default")
      (node (ref "P2") (pin "1") (pinfunction "1_1") (pintype "passive"))
      (node (ref "U3") (pin "10") (pinfunction "VOUTE_10") (pintype "tri_state"))
      (node (ref "U8") (pin "5") (pinfunction "+IN_B_5") (pintype "tri_state"))
    )
    (net (code "52") (name "/VGS4_x1") (class "Default")
      (node (ref "R14") (pin "1") (pinfunction "1_1") (pintype "passive"))
      (node (ref "R17") (pin "1") (pinfunction "1_1") (pintype "passive"))
      (node (ref "U11") (pin "12") (pinfunction "S3B_12") (pintype "passive"))
      (node (ref "U8") (pin "6") (pinfunction "-IN_B_6") (pintype "tri_state"))
    )
    (net (code "53") (name "/VGS4_x10") (class "Default")
      (node (ref "R17") (pin "2") (pinfunction "2_2") (pintype "passive"))
      (node (ref "U11") (pin "10") (pinfunction "S3A_10") (pintype "passive"))
    )
    (net (code "54") (name "/VGS5") (class "Default")
      (node (ref "P4") (pin "2") (pinfunction "2_2") (pintype "passive"))
      (node (ref "R23") (pin "1") (pinfunction "1_1") (pintype "passive"))
      (node (ref "U11") (pin "3") (pinfunction "D1_3") (pintype "passive"))
      (node (ref "U9") (pin "1") (pinfunction "OUT_A_1") (pintype "output"))
    )
    (net (code "55") (name "/VGS5_FILT") (class "Default")
      (node (ref "R23") (pin "2") (pinfunction "2_2") (pintype "passive"))
      (node (ref "S1") (pin "16") (pinfunction "NC6_16") (pintype "passive"))
    )
    (net (code "56") (name "/VGS5_RAW") (class "Default")
      (node (ref "P2") (pin "2") (pinfunction "2_2") (pintype "passive"))
      (node (ref "U3") (pin "12") (pinfunction "VOUTG_12") (pintype "tri_state"))
      (node (ref "U9") (pin "3") (pinfunction "+IN_A_3") (pintype "tri_state"))
    )
    (net (code "57") (name "/VGS5_x1") (class "Default")
      (node (ref "R11") (pin "1") (pinfunction "1_1") (pintype "passive"))
      (node (ref "R8") (pin "1") (pinfunction "1_1") (pintype "passive"))
      (node (ref "U11") (pin "4") (pinfunction "S1B_4") (pintype "passive"))
      (node (ref "U9") (pin "2") (pinfunction "-IN_A_2") (pintype "tri_state"))
    )
    (net (code "58") (name "/VGS5_x10") (class "Default")
      (node (ref "R11") (pin "2") (pinfunction "2_2") (pintype "passive"))
      (node (ref "U11") (pin "2") (pinfunction "S1A_2") (pintype "passive"))
    )
    (net (code "59") (name "/VGS6") (class "Default")
      (node (ref "P4") (pin "3") (pinfunction "3_3") (pintype "passive"))
      (node (ref "R25") (pin "1") (pinfunction "1_1") (pintype "passive"))
      (node (ref "U11") (pin "6") (pinfunction "D2_6") (pintype "passive"))
      (node (ref "U9") (pin "7") (pinfunction "OUT_B_7") (pintype "output"))
    )
    (net (code "60") (name "/VGS6_FILT") (class "Default")
      (node (ref "R25") (pin "2") (pinfunction "2_2") (pintype "passive"))
      (node (ref "S1") (pin "7") (pinfunction "NC3_7") (pintype "passive"))
    )
    (net (code "61") (name "/VGS6_RAW") (class "Default")
      (node (ref "P2") (pin "3") (pinfunction "3_3") (pintype "passive"))
      (node (ref "U3") (pin "11") (pinfunction "VOUTF_11") (pintype "tri_state"))
      (node (ref "U9") (pin "5") (pinfunction "+IN_B_5") (pintype "tri_state"))
    )
    (net (code "62") (name "/VGS6_x1") (class "Default")
      (node (ref "R15") (pin "1") (pinfunction "1_1") (pintype "passive"))
      (node (ref "R18") (pin "1") (pinfunction "1_1") (pintype "passive"))
      (node (ref "U11") (pin "5") (pinfunction "S2B_5") (pintype "passive"))
      (node (ref "U9") (pin "6") (pinfunction "-IN_B_6") (pintype "tri_state"))
    )
    (net (code "63") (name "/VGS6_x10") (class "Default")
      (node (ref "R18") (pin "2") (pinfunction "2_2") (pintype "passive"))
      (node (ref "U11") (pin "7") (pinfunction "S2A_7") (pintype "passive"))
    )
    (net (code "64") (name "/VMEAS") (class "Default")
      (node (ref "J1") (pin "12") (pinfunction "12_12") (pintype "passive"))
      (node (ref "J3") (pin "12") (pinfunction "12_12") (pintype "passive"))
      (node (ref "U4") (pin "8") (pinfunction "VIN_8") (pintype "input"))
    )
    (net (code "65") (name "1V_REF") (class "Default")
      (node (ref "C3") (pin "1") (pinfunction "1_1") (pintype "passive"))
      (node (ref "J1") (pin "05") (pinfunction "05_05") (pintype "passive"))
      (node (ref "J3") (pin "5") (pinfunction "5_5") (pintype "passive"))
      (node (ref "R13") (pin "2") (pinfunction "2_2") (pintype "passive"))
      (node (ref "R14") (pin "2") (pinfunction "2_2") (pintype "passive"))
      (node (ref "R15") (pin "2") (pinfunction "2_2") (pintype "passive"))
      (node (ref "R21") (pin "2") (pinfunction "2_2") (pintype "passive"))
      (node (ref "R7") (pin "2") (pinfunction "2_2") (pintype "passive"))
      (node (ref "R8") (pin "2") (pinfunction "2_2") (pintype "passive"))
      (node (ref "R9") (pin "2") (pinfunction "2_2") (pintype "passive"))
      (node (ref "U2") (pin "5") (pinfunction "OUT_5") (pintype "power_in"))
    )
    (net (code "66") (name "2V_REF") (class "Default")
      (node (ref "C1") (pin "1") (pinfunction "1_1") (pintype "passive"))
      (node (ref "C5") (pin "1") (pinfunction "1_1") (pintype "passive"))
      (node (ref "C6") (pin "1") (pinfunction "1_1") (pintype "passive"))
      (node (ref "C7") (pin "1") (pinfunction "1_1") (pintype "passive"))
      (node (ref "J1") (pin "06") (pinfunction "06_06") (pintype "passive"))
      (node (ref "J3") (pin "6") (pinfunction "6_6") (pintype "passive"))
      (node (ref "U1") (pin "5") (pinfunction "VOUT_5") (pintype "output"))
      (node (ref "U3") (pin "8") (pinfunction "VREFABCD_8") (pintype "input"))
      (node (ref "U3") (pin "9") (pinfunction "VREFEFGH_9") (pintype "input"))
      (node (ref "U4") (pin "5") (pinfunction "VREF_5") (pintype "input"))
    )
    (net (code "67") (name "3V3") (class "Default")
      (node (ref "C14") (pin "1") (pinfunction "1_1") (pintype "passive"))
      (node (ref "C2") (pin "1") (pinfunction "1_1") (pintype "passive"))
      (node (ref "C4") (pin "1") (pinfunction "1_1") (pintype "passive"))
      (node (ref "C8") (pin "1") (pinfunction "1_1") (pintype "passive"))
      (node (ref "C9") (pin "1") (pinfunction "1_1") (pintype "passive"))
      (node (ref "J1") (pin "03") (pinfunction "03_03") (pintype "passive"))
      (node (ref "J1") (pin "04") (pinfunction "04_04") (pintype "passive"))
      (node (ref "J3") (pin "3") (pinfunction "3_3") (pintype "passive"))
      (node (ref "J3") (pin "4") (pinfunction "4_4") (pintype "passive"))
      (node (ref "L1") (pin "1") (pinfunction "1_1") (pintype "passive"))
      (node (ref "L2") (pin "1") (pinfunction "1_1") (pintype "passive"))
      (node (ref "U1") (pin "1") (pinfunction "VIN_1") (pintype "tri_state"))
      (node (ref "U1") (pin "3") (pinfunction "EN_3") (pintype "input"))
      (node (ref "U2") (pin "1") (pinfunction "IN_1") (pintype "power_in"))
      (node (ref "U2") (pin "3") (pinfunction "EN_3") (pintype "input"))
      (node (ref "U3") (pin "3") (pinfunction "VDD_3") (pintype "power_in"))
      (node (ref "U4") (pin "1") (pinfunction "VDD_1") (pintype "power_in"))
      (node (ref "U6") (pin "8") (pinfunction "VIN_8") (pintype "power_in"))
    )
    (net (code "68") (name "GND") (class "Default")
      (node (ref "C1") (pin "2") (pinfunction "2_2") (pintype "passive"))
      (node (ref "C13") (pin "1") (pinfunction "1_1") (pintype "passive"))
      (node (ref "C14") (pin "2") (pinfunction "2_2") (pintype "passive"))
      (node (ref "C15") (pin "2") (pinfunction "2_2") (pintype "passive"))
      (node (ref "C17") (pin "1") (pinfunction "1_1") (pintype "passive"))
      (node (ref "C18") (pin "1") (pinfunction "1_1") (pintype "passive"))
      (node (ref "C19") (pin "1") (pinfunction "1_1") (pintype "passive"))
      (node (ref "C2") (pin "2") (pinfunction "2_2") (pintype "passive"))
      (node (ref "C20") (pin "1") (pinfunction "1_1") (pintype "passive"))
      (node (ref "C21") (pin "1") (pinfunction "1_1") (pintype "passive"))
      (node (ref "C22") (pin "1") (pinfunction "1_1") (pintype "passive"))
      (node (ref "C24") (pin "1") (pinfunction "1_1") (pintype "passive"))
      (node (ref "C25") (pin "1") (pinfunction "1_1") (pintype "passive"))
      (node (ref "C26") (pin "1") (pinfunction "1_1") (pintype "passive"))
      (node (ref "C27") (pin "1") (pinfunction "1_1") (pintype "passive"))
      (node (ref "C3") (pin "2") (pinfunction "2_2") (pintype "passive"))
      (node (ref "C4") (pin "2") (pinfunction "2_2") (pintype "passive"))
      (node (ref "C5") (pin "2") (pinfunction "2_2") (pintype "passive"))
      (node (ref "C6") (pin "2") (pinfunction "2_2") (pintype "passive"))
      (node (ref "C7") (pin "2") (pinfunction "2_2") (pintype "passive"))
      (node (ref "C8") (pin "2") (pinfunction "2_2") (pintype "passive"))
      (node (ref "C9") (pin "2") (pinfunction "2_2") (pintype "passive"))
      (node (ref "D2") (pin "1") (pinfunction "C_1") (pintype "passive"))
      (node (ref "J1") (pin "01") (pinfunction "01_01") (pintype "passive"))
      (node (ref "J1") (pin "02") (pinfunction "02_02") (pintype "passive"))
      (node (ref "J1") (pin "07") (pinfunction "07_07") (pintype "passive"))
      (node (ref "J1") (pin "08") (pinfunction "08_08") (pintype "passive"))
      (node (ref "J1") (pin "11") (pinfunction "11_11") (pintype "passive"))
      (node (ref "J1") (pin "13") (pinfunction "13_13") (pintype "passive"))
      (node (ref "J1") (pin "14") (pinfunction "14_14") (pintype "passive"))
      (node (ref "J1") (pin "16") (pinfunction "16_16") (pintype "passive"))
      (node (ref "J1") (pin "19") (pinfunction "19_19") (pintype "passive"))
      (node (ref "J1") (pin "24") (pinfunction "24_24") (pintype "passive"))
      (node (ref "J1") (pin "27") (pinfunction "27_27") (pintype "passive"))
      (node (ref "J2") (pin "01") (pinfunction "01_01") (pintype "passive"))
      (node (ref "J2") (pin "02") (pinfunction "02_02") (pintype "passive"))
      (node (ref "J2") (pin "07") (pinfunction "07_07") (pintype "passive"))
      (node (ref "J2") (pin "08") (pinfunction "08_08") (pintype "passive"))
      (node (ref "J2") (pin "11") (pinfunction "11_11") (pintype "passive"))
      (node (ref "J2") (pin "12") (pinfunction "12_12") (pintype "passive"))
      (node (ref "J2") (pin "15") (pinfunction "15_15") (pintype "passive"))
      (node (ref "J2") (pin "16") (pinfunction "16_16") (pintype "passive"))
      (node (ref "J2") (pin "20") (pinfunction "20_20") (pintype "passive"))
      (node (ref "J2") (pin "23") (pinfunction "23_23") (pintype "passive"))
      (node (ref "J2") (pin "28") (pinfunction "28_28") (pintype "passive"))
      (node (ref "J3") (pin "1") (pinfunction "1_1") (pintype "passive"))
      (node (ref "J3") (pin "11") (pinfunction "11_11") (pintype "passive"))
      (node (ref "J3") (pin "13") (pinfunction "13_13") (pintype "passive"))
      (node (ref "J3") (pin "14") (pinfunction "14_14") (pintype "passive"))
      (node (ref "J3") (pin "16") (pinfunction "16_16") (pintype "passive"))
      (node (ref "J3") (pin "19") (pinfunction "19_19") (pintype "passive"))
      (node (ref "J3") (pin "2") (pinfunction "2_2") (pintype "passive"))
      (node (ref "J3") (pin "24") (pinfunction "24_24") (pintype "passive"))
      (node (ref "J3") (pin "27") (pinfunction "27_27") (pintype "passive"))
      (node (ref "J3") (pin "7") (pinfunction "7_7") (pintype "passive"))
      (node (ref "J3") (pin "8") (pinfunction "8_8") (pintype "passive"))
      (node (ref "J4") (pin "1") (pinfunction "1_1") (pintype "passive"))
      (node (ref "J4") (pin "11") (pinfunction "11_11") (pintype "passive"))
      (node (ref "J4") (pin "12") (pinfunction "12_12") (pintype "passive"))
      (node (ref "J4") (pin "15") (pinfunction "15_15") (pintype "passive"))
      (node (ref "J4") (pin "16") (pinfunction "16_16") (pintype "passive"))
      (node (ref "J4") (pin "2") (pinfunction "2_2") (pintype "passive"))
      (node (ref "J4") (pin "20") (pinfunction "20_20") (pintype "passive"))
      (node (ref "J4") (pin "23") (pinfunction "23_23") (pintype "passive"))
      (node (ref "J4") (pin "28") (pinfunction "28_28") (pintype "passive"))
      (node (ref "J4") (pin "7") (pinfunction "7_7") (pintype "passive"))
      (node (ref "J4") (pin "8") (pinfunction "8_8") (pintype "passive"))
      (node (ref "R19") (pin "2") (pinfunction "2_2") (pintype "passive"))
      (node (ref "R21") (pin "1") (pinfunction "1_1") (pintype "passive"))
      (node (ref "R3") (pin "1") (pinfunction "1_1") (pintype "passive"))
      (node (ref "R4") (pin "1") (pinfunction "1_1") (pintype "passive"))
      (node (ref "R5") (pin "2") (pinfunction "2_2") (pintype "passive"))
      (node (ref "U1") (pin "2") (pinfunction "GND_2") (pintype "power_in"))
      (node (ref "U10") (pin "16") (pinfunction "GND_16") (pintype "power_in"))
      (node (ref "U11") (pin "16") (pinfunction "GND_16") (pintype "power_in"))
      (node (ref "U2") (pin "2") (pinfunction "GND_2") (pintype "power_in"))
      (node (ref "U3") (pin "1") (pinfunction "~{LDAC}_1") (pintype "input"))
      (node (ref "U3") (pin "14") (pinfunction "GND_14") (pintype "power_in"))
      (node (ref "U4") (pin "4") (pinfunction "AGND_4") (pintype "power_in"))
      (node (ref "U4") (pin "7") (pinfunction "DGND_7") (pintype "power_in"))
      (node (ref "U6") (pin "3") (pinfunction "GND_3") (pintype "power_in"))
      (node (ref "U6") (pin "7") (pinfunction "PGND_7") (pintype "power_in"))
      (node (ref "U6") (pin "9") (pinfunction "PGND_9") (pintype "power_in"))
    )
    (net (code "69") (name "Net-(D1-C)") (class "Default")
      (node (ref "C11") (pin "2") (pinfunction "2_2") (pintype "passive"))
      (node (ref "D1") (pin "1") (pinfunction "C_1") (pintype "passive"))
      (node (ref "D2") (pin "2") (pinfunction "A_2") (pintype "passive"))
    )
    (net (code "70") (name "Net-(D3-A)") (class "Default")
      (node (ref "D3") (pin "2") (pinfunction "A_2") (pintype "passive"))
      (node (ref "L2") (pin "2") (pinfunction "2_2") (pintype "passive"))
      (node (ref "U6") (pin "6") (pinfunction "SW2_6") (pintype "power_in"))
    )
    (net (code "71") (name "Net-(U4-SDATA)") (class "Default")
      (node (ref "R1") (pin "1") (pinfunction "1_1") (pintype "passive"))
      (node (ref "U4") (pin "2") (pinfunction "SDATA_2") (pintype "tri_state"))
    )
    (net (code "72") (name "Net-(U6-FB2)") (class "Default")
      (node (ref "C16") (pin "2") (pinfunction "2_2") (pintype "passive"))
      (node (ref "R5") (pin "1") (pinfunction "1_1") (pintype "passive"))
      (node (ref "R6") (pin "2") (pinfunction "2_2") (pintype "passive"))
      (node (ref "U6") (pin "5") (pinfunction "FB2_5") (pintype "input"))
    )
    (net (code "73") (name "Net-(U6-NFB1)") (class "Default")
      (node (ref "C12") (pin "2") (pinfunction "2_2") (pintype "passive"))
      (node (ref "R2") (pin "1") (pinfunction "1_1") (pintype "passive"))
      (node (ref "R3") (pin "2") (pinfunction "2_2") (pintype "passive"))
      (node (ref "U6") (pin "1") (pinfunction "NFB1_1") (pintype "input"))
    )
    (net (code "74") (name "Net-(U6-SW1)") (class "Default")
      (node (ref "C11") (pin "1") (pinfunction "1_1") (pintype "passive"))
      (node (ref "L1") (pin "2") (pinfunction "2_2") (pintype "passive"))
      (node (ref "U6") (pin "10") (pinfunction "SW1_10") (pintype "power_in"))
    )
    (net (code "75") (name "unconnected-(S1-NO1-Pad3)") (class "Default")
      (node (ref "S1") (pin "3") (pinfunction "NO1_3") (pintype "passive"))
    )
    (net (code "76") (name "unconnected-(S1-NO2-Pad6)") (class "Default")
      (node (ref "S1") (pin "6") (pinfunction "NO2_6") (pintype "passive"))
    )
    (net (code "77") (name "unconnected-(S1-NO3-Pad9)") (class "Default")
      (node (ref "S1") (pin "9") (pinfunction "NO3_9") (pintype "passive"))
    )
    (net (code "78") (name "unconnected-(S1-NO4-Pad12)") (class "Default")
      (node (ref "S1") (pin "12") (pinfunction "NO4_12") (pintype "passive"))
    )
    (net (code "79") (name "unconnected-(S1-NO5-Pad15)") (class "Default")
      (node (ref "S1") (pin "15") (pinfunction "NO5_15") (pintype "passive"))
    )
    (net (code "80") (name "unconnected-(S1-NO6-Pad18)") (class "Default")
      (node (ref "S1") (pin "18") (pinfunction "NO6_18") (pintype "passive"))
    )
    (net (code "81") (name "unconnected-(S1-SHIELD-PadS1)") (class "Default")
      (node (ref "S1") (pin "S1") (pinfunction "SHIELD_S1") (pintype "passive+no_connect"))
    )
    (net (code "82") (name "unconnected-(S1-SHIELD-PadS2)") (class "Default")
      (node (ref "S1") (pin "S2") (pinfunction "SHIELD_S2") (pintype "passive+no_connect"))
    )
    (net (code "83") (name "unconnected-(S1-SHIELD-PadS3)") (class "Default")
      (node (ref "S1") (pin "S3") (pinfunction "SHIELD_S3") (pintype "passive+no_connect"))
    )
    (net (code "84") (name "unconnected-(S1-SHIELD-PadS4)") (class "Default")
      (node (ref "S1") (pin "S4") (pinfunction "SHIELD_S4") (pintype "passive+no_connect"))
    )
    (net (code "85") (name "unconnected-(U1-NC-Pad4)") (class "Default")
      (node (ref "U1") (pin "4") (pinfunction "NC_4") (pintype "passive"))
    )
    (net (code "86") (name "unconnected-(U2-NC-Pad4)") (class "Default")
      (node (ref "U2") (pin "4") (pinfunction "NC_4") (pintype "passive"))
    )
    (net (code "87") (name "unconnected-(U3-VOUTH-Pad13)") (class "Default")
      (node (ref "U3") (pin "13") (pinfunction "VOUTH_13") (pintype "tri_state"))
    )
  )
)
